# Mux.net
KiCad netlist of a schematic drawn in Altium Designer
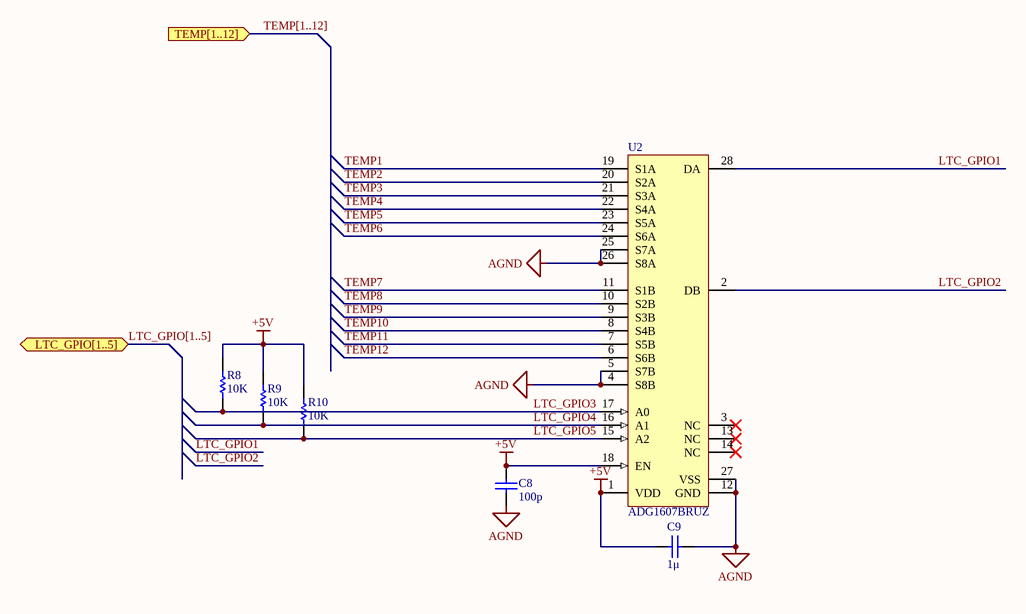
[diagram p0: Mux.SchDoc]

(export (version "E")
  (design (tool "Eeschema 10.0.6"))
  (components
    (comp (ref "C8")
      (value "100p")
      (footprint "CAPC0603(1608)55_N")
      (description "Keramikvielschichtkondensator, SMD, Baureihe MC, ± 5%")
      (fields (field (name "MANUFACTURER") "TDK") (field (name "TOLERANCE") "± 5%"))
      (libsource (lib "Res&Caps") (part "Cap 100p"))
    )
    (comp (ref "C9")
      (value "1μ")
      (footprint "CAPC0603(1608)55_N")
      (description "Keramikvielschichtkondensator, SMD, Baureihe MC, ± 10%")
      (fields (field (name "MANUFACTURER") "TDK") (field (name "TOLERANCE") "± 10%"))
      (libsource (lib "Res&Caps") (part "Cap 1μ"))
    )
    (comp (ref "R8")
      (value "10K")
      (footprint "RESC0603(1608)_N")
      (description "Chipwiderstand, SMD, Baureihe MC, 1%")
      (fields (field (name "MANUFACTURER") "Multicomp") (field (name "POWER") "100mW"))
      (libsource (lib "Res&Caps") (part "Res 10K"))
    )
    (comp (ref "R9")
      (value "10K")
      (footprint "RESC0603(1608)_N")
      (description "Chipwiderstand, SMD, Baureihe MC, 1%")
      (fields (field (name "MANUFACTURER") "Multicomp") (field (name "POWER") "100mW"))
      (libsource (lib "Res&Caps") (part "Res 10K"))
    )
    (comp (ref "R10")
      (value "10K")
      (footprint "RESC0603(1608)_N")
      (description "Chipwiderstand, SMD, Baureihe MC, 1%")
      (fields (field (name "MANUFACTURER") "Multicomp") (field (name "POWER") "100mW"))
      (libsource (lib "Res&Caps") (part "Res 10K"))
    )
    (comp (ref "U2")
      (value "ADG1607BRUZ")
      (footprint "ADI-RU-28_M")
      (fields (field (name "MANUFACTURER") "Analog Devices"))
      (libsource (lib "Altium Content Vault") (part "ADI-ADG1607-RU-28"))
    )
  )
  (nets
    (net (code "1") (name "+5V") (class "Default")
      (node (ref "C8") (pin "2") (pinfunction "2_2") (pintype "passive"))
      (node (ref "C9") (pin "1") (pinfunction "1_1") (pintype "passive"))
      (node (ref "R10") (pin "2") (pinfunction "2_2") (pintype "passive"))
      (node (ref "R8") (pin "2") (pinfunction "2_2") (pintype "passive"))
      (node (ref "R9") (pin "2") (pinfunction "2_2") (pintype "passive"))
      (node (ref "U2") (pin "1") (pinfunction "VDD_1") (pintype "power_in"))
      (node (ref "U2") (pin "18") (pinfunction "EN_18") (pintype "input"))
    )
    (net (code "2") (name "/LTC_GPIO1") (class "Default")
      (node (ref "U2") (pin "28") (pinfunction "DA_28") (pintype "passive"))
    )
    (net (code "3") (name "/LTC_GPIO2") (class "Default")
      (node (ref "U2") (pin "2") (pinfunction "DB_2") (pintype "passive"))
    )
    (net (code "4") (name "/LTC_GPIO3") (class "Default")
      (node (ref "R8") (pin "1") (pinfunction "1_1") (pintype "passive"))
      (node (ref "U2") (pin "17") (pinfunction "A0_17") (pintype "input"))
    )
    (net (code "5") (name "/LTC_GPIO4") (class "Default")
      (node (ref "R9") (pin "1") (pinfunction "1_1") (pintype "passive"))
      (node (ref "U2") (pin "16") (pinfunction "A1_16") (pintype "input"))
    )
    (net (code "6") (name "/LTC_GPIO5") (class "Default")
      (node (ref "R10") (pin "1") (pinfunction "1_1") (pintype "passive"))
      (node (ref "U2") (pin "15") (pinfunction "A2_15") (pintype "input"))
    )
    (net (code "8") (name "/TEMP1") (class "Default")
      (node (ref "U2") (pin "19") (pinfunction "S1A_19") (pintype "passive"))
    )
    (net (code "9") (name "/TEMP2") (class "Default")
      (node (ref "U2") (pin "20") (pinfunction "S2A_20") (pintype "passive"))
    )
    (net (code "10") (name "/TEMP3") (class "Default")
      (node (ref "U2") (pin "21") (pinfunction "S3A_21") (pintype "passive"))
    )
    (net (code "11") (name "/TEMP4") (class "Default")
      (node (ref "U2") (pin "22") (pinfunction "S4A_22") (pintype "passive"))
    )
    (net (code "12") (name "/TEMP5") (class "Default")
      (node (ref "U2") (pin "23") (pinfunction "S5A_23") (pintype "passive"))
    )
    (net (code "13") (name "/TEMP6") (class "Default")
      (node (ref "U2") (pin "24") (pinfunction "S6A_24") (pintype "passive"))
    )
    (net (code "14") (name "/TEMP7") (class "Default")
      (node (ref "U2") (pin "11") (pinfunction "S1B_11") (pintype "passive"))
    )
    (net (code "15") (name "/TEMP8") (class "Default")
      (node (ref "U2") (pin "10") (pinfunction "S2B_10") (pintype "passive"))
    )
    (net (code "16") (name "/TEMP9") (class "Default")
      (node (ref "U2") (pin "9") (pinfunction "S3B_9") (pintype "passive"))
    )
    (net (code "17") (name "/TEMP10") (class "Default")
      (node (ref "U2") (pin "8") (pinfunction "S4B_8") (pintype "passive"))
    )
    (net (code "18") (name "/TEMP11") (class "Default")
      (node (ref "U2") (pin "7") (pinfunction "S5B_7") (pintype "passive"))
    )
    (net (code "19") (name "/TEMP12") (class "Default")
      (node (ref "U2") (pin "6") (pinfunction "S6B_6") (pintype "passive"))
    )
    (net (code "21") (name "AGND") (class "Default")
      (node (ref "C8") (pin "1") (pinfunction "1_1") (pintype "passive"))
      (node (ref "C9") (pin "2") (pinfunction "2_2") (pintype "passive"))
      (node (ref "U2") (pin "12") (pinfunction "GND_12") (pintype "power_in"))
      (node (ref "U2") (pin "25") (pinfunction "S7A_25") (pintype "passive"))
      (node (ref "U2") (pin "26") (pinfunction "S8A_26") (pintype "passive"))
      (node (ref "U2") (pin "27") (pinfunction "VSS_27") (pintype "power_in"))
      (node (ref "U2") (pin "4") (pinfunction "S8B_4") (pintype "passive"))
      (node (ref "U2") (pin "5") (pinfunction "S7B_5") (pintype "passive"))
    )
    (net (code "22") (name "unconnected-(U2-NC-Pad3)") (class "Default")
      (node (ref "U2") (pin "3") (pinfunction "NC_3") (pintype "passive+no_connect"))
    )
    (net (code "23") (name "unconnected-(U2-NC-Pad13)") (class "Default")
      (node (ref "U2") (pin "13") (pinfunction "NC_13") (pintype "passive+no_connect"))
    )
    (net (code "24") (name "unconnected-(U2-NC-Pad14)") (class "Default")
      (node (ref "U2") (pin "14") (pinfunction "NC_14") (pintype "passive+no_connect"))
    )
  )
)
